# FPGA.net
KiCad netlist of a schematic drawn in Altium Designer
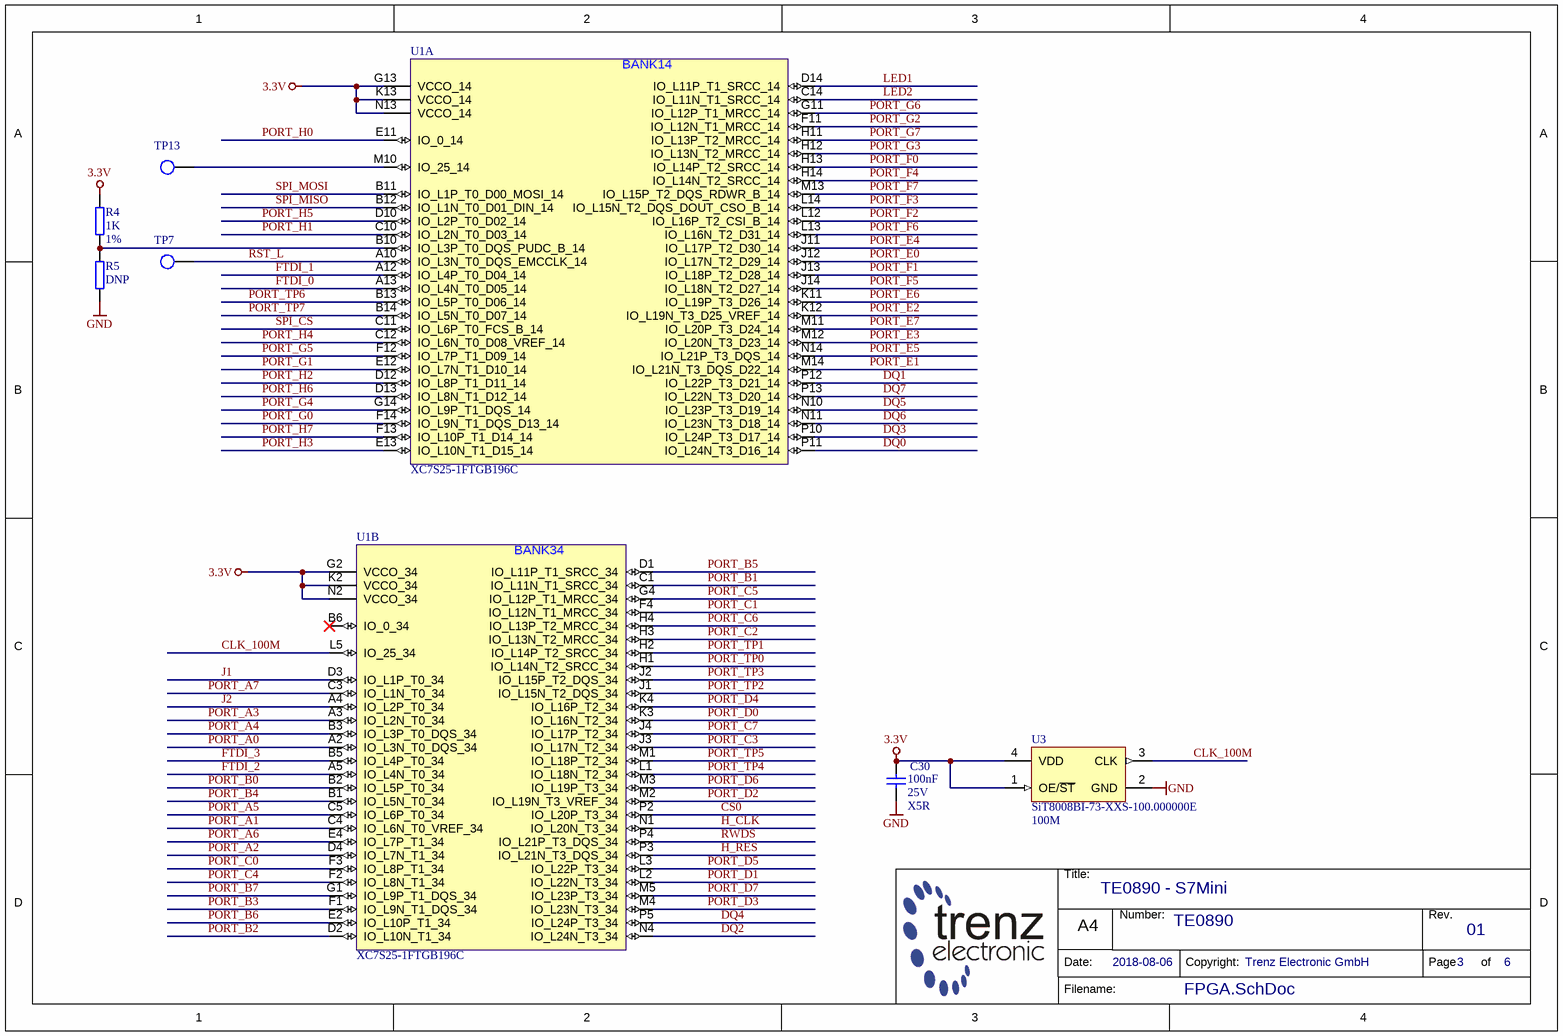
[diagram p0: FPGA.SchDoc]

(export (version "E")
  (design (tool "Eeschema 10.0.6"))
  (components
    (comp (ref "C30")
      (value "100nF")
      (footprint "CAPC1005X55N")
      (description "KON 100nF 25V X5R ±10% SMD BF 1005 (0402)")
      (fields (field (name "VOLTAGE") "25V") (field (name "TECHNOLOGY") "X5R"))
      (libsource (lib "TE") (part "CAP-NP"))
    )
    (comp (ref "R4")
      (value "1K")
      (footprint "RESC1005X40N")
      (description "WID SMD 1K 1% 0,063W  BF 1005 (0402)")
      (fields (field (name "TOLERANCE") "1%"))
      (libsource (lib "TE") (part "RES"))
    )
    (comp (ref "R5")
      (value "DNP")
      (footprint "RESC1005X40N")
      (description "WID SMD BF 1005 (0402) DNP")
      (libsource (lib "TE") (part "RES-NO_BOM"))
    )
    (comp (ref "TP7")
      (value "Testpoint 0.8mm THT")
      (footprint "TP_0.8mm_THT")
      (description "Testpoint 0.8mm TH")
      (libsource (lib "TE") (part "TP_THT"))
    )
    (comp (ref "TP13")
      (value "Testpoint 0.8mm THT")
      (footprint "TP_0.8mm_THT")
      (description "Testpoint 0.8mm TH")
      (libsource (lib "TE") (part "TP_THT"))
    )
    (comp (ref "U1")
      (value "XC7S25-1FTGB196C")
      (footprint "BGA196C100P14X14_1500X1500X155B50N")
      (libsource (lib "TE") (part "XC7S25-1FTGB196"))
    )
    (comp (ref "U3")
      (value "SiT8008BI-73-XXS-100.000000E")
      (footprint "2016")
      (description "SiT8008BI-73-XXS-100.000000E MEMS Oszillator 100MHz")
      (fields (field (name "ALTIUM_VALUE") "100M"))
      (libsource (lib "TE") (part "SiT8103"))
    )
  )
  (nets
    (net (code "1") (name "/CLK_100M") (class "Default")
      (node (ref "U1") (pin "L5") (pinfunction "IO_25_34_L5") (pintype "bidirectional"))
      (node (ref "U3") (pin "3") (pinfunction "CLK_3") (pintype "output"))
    )
    (net (code "2") (name "/CS0") (class "Default")
      (node (ref "U1") (pin "P2") (pinfunction "IO_L20P_T3_34_P2") (pintype "bidirectional"))
    )
    (net (code "3") (name "/DQ0") (class "Default")
      (node (ref "U1") (pin "P11") (pinfunction "IO_L24N_T3_D16_14_P11") (pintype "bidirectional"))
    )
    (net (code "4") (name "/DQ1") (class "Default")
      (node (ref "U1") (pin "P12") (pinfunction "IO_L22P_T3_D21_14_P12") (pintype "bidirectional"))
    )
    (net (code "5") (name "/DQ2") (class "Default")
      (node (ref "U1") (pin "N4") (pinfunction "IO_L24N_T3_34_N4") (pintype "bidirectional"))
    )
    (net (code "6") (name "/DQ3") (class "Default")
      (node (ref "U1") (pin "P10") (pinfunction "IO_L24P_T3_D17_14_P10") (pintype "bidirectional"))
    )
    (net (code "7") (name "/DQ4") (class "Default")
      (node (ref "U1") (pin "P5") (pinfunction "IO_L24P_T3_34_P5") (pintype "bidirectional"))
    )
    (net (code "8") (name "/DQ5") (class "Default")
      (node (ref "U1") (pin "N10") (pinfunction "IO_L23P_T3_D19_14_N10") (pintype "bidirectional"))
    )
    (net (code "9") (name "/DQ6") (class "Default")
      (node (ref "U1") (pin "N11") (pinfunction "IO_L23N_T3_D18_14_N11") (pintype "bidirectional"))
    )
    (net (code "10") (name "/DQ7") (class "Default")
      (node (ref "U1") (pin "P13") (pinfunction "IO_L22N_T3_D20_14_P13") (pintype "bidirectional"))
    )
    (net (code "11") (name "/FTDI_0") (class "Default")
      (node (ref "U1") (pin "A13") (pinfunction "IO_L4N_T0_D05_14_A13") (pintype "bidirectional"))
    )
    (net (code "12") (name "/FTDI_1") (class "Default")
      (node (ref "U1") (pin "A12") (pinfunction "IO_L4P_T0_D04_14_A12") (pintype "bidirectional"))
    )
    (net (code "13") (name "/FTDI_2") (class "Default")
      (node (ref "U1") (pin "A5") (pinfunction "IO_L4N_T0_34_A5") (pintype "bidirectional"))
    )
    (net (code "14") (name "/FTDI_3") (class "Default")
      (node (ref "U1") (pin "B5") (pinfunction "IO_L4P_T0_34_B5") (pintype "bidirectional"))
    )
    (net (code "15") (name "/H_CLK") (class "Default")
      (node (ref "U1") (pin "N1") (pinfunction "IO_L20N_T3_34_N1") (pintype "bidirectional"))
    )
    (net (code "16") (name "/H_RES") (class "Default")
      (node (ref "U1") (pin "P3") (pinfunction "IO_L21N_T3_DQS_34_P3") (pintype "bidirectional"))
    )
    (net (code "17") (name "/J1") (class "Default")
      (node (ref "U1") (pin "D3") (pinfunction "IO_L1P_T0_34_D3") (pintype "bidirectional"))
    )
    (net (code "18") (name "/J2") (class "Default")
      (node (ref "U1") (pin "A4") (pinfunction "IO_L2P_T0_34_A4") (pintype "bidirectional"))
    )
    (net (code "19") (name "/LED1") (class "Default")
      (node (ref "U1") (pin "D14") (pinfunction "IO_L11P_T1_SRCC_14_D14") (pintype "bidirectional"))
    )
    (net (code "20") (name "/LED2") (class "Default")
      (node (ref "U1") (pin "C14") (pinfunction "IO_L11N_T1_SRCC_14_C14") (pintype "bidirectional"))
    )
    (net (code "21") (name "/PORT_A0") (class "Default")
      (node (ref "U1") (pin "A2") (pinfunction "IO_L3N_T0_DQS_34_A2") (pintype "bidirectional"))
    )
    (net (code "22") (name "/PORT_A1") (class "Default")
      (node (ref "U1") (pin "C4") (pinfunction "IO_L6N_T0_VREF_34_C4") (pintype "bidirectional"))
    )
    (net (code "23") (name "/PORT_A2") (class "Default")
      (node (ref "U1") (pin "D4") (pinfunction "IO_L7N_T1_34_D4") (pintype "bidirectional"))
    )
    (net (code "24") (name "/PORT_A3") (class "Default")
      (node (ref "U1") (pin "A3") (pinfunction "IO_L2N_T0_34_A3") (pintype "bidirectional"))
    )
    (net (code "25") (name "/PORT_A4") (class "Default")
      (node (ref "U1") (pin "B3") (pinfunction "IO_L3P_T0_DQS_34_B3") (pintype "bidirectional"))
    )
    (net (code "26") (name "/PORT_A5") (class "Default")
      (node (ref "U1") (pin "C5") (pinfunction "IO_L6P_T0_34_C5") (pintype "bidirectional"))
    )
    (net (code "27") (name "/PORT_A6") (class "Default")
      (node (ref "U1") (pin "E4") (pinfunction "IO_L7P_T1_34_E4") (pintype "bidirectional"))
    )
    (net (code "28") (name "/PORT_A7") (class "Default")
      (node (ref "U1") (pin "C3") (pinfunction "IO_L1N_T0_34_C3") (pintype "bidirectional"))
    )
    (net (code "29") (name "/PORT_B0") (class "Default")
      (node (ref "U1") (pin "B2") (pinfunction "IO_L5P_T0_34_B2") (pintype "bidirectional"))
    )
    (net (code "30") (name "/PORT_B1") (class "Default")
      (node (ref "U1") (pin "C1") (pinfunction "IO_L11N_T1_SRCC_34_C1") (pintype "bidirectional"))
    )
    (net (code "31") (name "/PORT_B2") (class "Default")
      (node (ref "U1") (pin "D2") (pinfunction "IO_L10N_T1_34_D2") (pintype "bidirectional"))
    )
    (net (code "32") (name "/PORT_B3") (class "Default")
      (node (ref "U1") (pin "F1") (pinfunction "IO_L9N_T1_DQS_34_F1") (pintype "bidirectional"))
    )
    (net (code "33") (name "/PORT_B4") (class "Default")
      (node (ref "U1") (pin "B1") (pinfunction "IO_L5N_T0_34_B1") (pintype "bidirectional"))
    )
    (net (code "34") (name "/PORT_B5") (class "Default")
      (node (ref "U1") (pin "D1") (pinfunction "IO_L11P_T1_SRCC_34_D1") (pintype "bidirectional"))
    )
    (net (code "35") (name "/PORT_B6") (class "Default")
      (node (ref "U1") (pin "E2") (pinfunction "IO_L10P_T1_34_E2") (pintype "bidirectional"))
    )
    (net (code "36") (name "/PORT_B7") (class "Default")
      (node (ref "U1") (pin "G1") (pinfunction "IO_L9P_T1_DQS_34_G1") (pintype "bidirectional"))
    )
    (net (code "37") (name "/PORT_C0") (class "Default")
      (node (ref "U1") (pin "F3") (pinfunction "IO_L8P_T1_34_F3") (pintype "bidirectional"))
    )
    (net (code "38") (name "/PORT_C1") (class "Default")
      (node (ref "U1") (pin "F4") (pinfunction "IO_L12N_T1_MRCC_34_F4") (pintype "bidirectional"))
    )
    (net (code "39") (name "/PORT_C2") (class "Default")
      (node (ref "U1") (pin "H3") (pinfunction "IO_L13N_T2_MRCC_34_H3") (pintype "bidirectional"))
    )
    (net (code "40") (name "/PORT_C3") (class "Default")
      (node (ref "U1") (pin "J3") (pinfunction "IO_L17N_T2_34_J3") (pintype "bidirectional"))
    )
    (net (code "41") (name "/PORT_C4") (class "Default")
      (node (ref "U1") (pin "F2") (pinfunction "IO_L8N_T1_34_F2") (pintype "bidirectional"))
    )
    (net (code "42") (name "/PORT_C5") (class "Default")
      (node (ref "U1") (pin "G4") (pinfunction "IO_L12P_T1_MRCC_34_G4") (pintype "bidirectional"))
    )
    (net (code "43") (name "/PORT_C6") (class "Default")
      (node (ref "U1") (pin "H4") (pinfunction "IO_L13P_T2_MRCC_34_H4") (pintype "bidirectional"))
    )
    (net (code "44") (name "/PORT_C7") (class "Default")
      (node (ref "U1") (pin "J4") (pinfunction "IO_L17P_T2_34_J4") (pintype "bidirectional"))
    )
    (net (code "45") (name "/PORT_D0") (class "Default")
      (node (ref "U1") (pin "K3") (pinfunction "IO_L16N_T2_34_K3") (pintype "bidirectional"))
    )
    (net (code "46") (name "/PORT_D1") (class "Default")
      (node (ref "U1") (pin "L2") (pinfunction "IO_L22N_T3_34_L2") (pintype "bidirectional"))
    )
    (net (code "47") (name "/PORT_D2") (class "Default")
      (node (ref "U1") (pin "M2") (pinfunction "IO_L19N_T3_VREF_34_M2") (pintype "bidirectional"))
    )
    (net (code "48") (name "/PORT_D3") (class "Default")
      (node (ref "U1") (pin "M4") (pinfunction "IO_L23N_T3_34_M4") (pintype "bidirectional"))
    )
    (net (code "49") (name "/PORT_D4") (class "Default")
      (node (ref "U1") (pin "K4") (pinfunction "IO_L16P_T2_34_K4") (pintype "bidirectional"))
    )
    (net (code "50") (name "/PORT_D5") (class "Default")
      (node (ref "U1") (pin "L3") (pinfunction "IO_L22P_T3_34_L3") (pintype "bidirectional"))
    )
    (net (code "51") (name "/PORT_D6") (class "Default")
      (node (ref "U1") (pin "M3") (pinfunction "IO_L19P_T3_34_M3") (pintype "bidirectional"))
    )
    (net (code "52") (name "/PORT_D7") (class "Default")
      (node (ref "U1") (pin "M5") (pinfunction "IO_L23P_T3_34_M5") (pintype "bidirectional"))
    )
    (net (code "53") (name "/PORT_E0") (class "Default")
      (node (ref "U1") (pin "J12") (pinfunction "IO_L17N_T2_D29_14_J12") (pintype "bidirectional"))
    )
    (net (code "54") (name "/PORT_E1") (class "Default")
      (node (ref "U1") (pin "M14") (pinfunction "IO_L21N_T3_DQS_D22_14_M14") (pintype "bidirectional"))
    )
    (net (code "55") (name "/PORT_E2") (class "Default")
      (node (ref "U1") (pin "K12") (pinfunction "IO_L19N_T3_D25_VREF_14_K12") (pintype "bidirectional"))
    )
    (net (code "56") (name "/PORT_E3") (class "Default")
      (node (ref "U1") (pin "M12") (pinfunction "IO_L20N_T3_D23_14_M12") (pintype "bidirectional"))
    )
    (net (code "57") (name "/PORT_E4") (class "Default")
      (node (ref "U1") (pin "J11") (pinfunction "IO_L17P_T2_D30_14_J11") (pintype "bidirectional"))
    )
    (net (code "58") (name "/PORT_E5") (class "Default")
      (node (ref "U1") (pin "N14") (pinfunction "IO_L21P_T3_DQS_14_N14") (pintype "bidirectional"))
    )
    (net (code "59") (name "/PORT_E6") (class "Default")
      (node (ref "U1") (pin "K11") (pinfunction "IO_L19P_T3_D26_14_K11") (pintype "bidirectional"))
    )
    (net (code "60") (name "/PORT_E7") (class "Default")
      (node (ref "U1") (pin "M11") (pinfunction "IO_L20P_T3_D24_14_M11") (pintype "bidirectional"))
    )
    (net (code "61") (name "/PORT_F0") (class "Default")
      (node (ref "U1") (pin "H13") (pinfunction "IO_L14P_T2_SRCC_14_H13") (pintype "bidirectional"))
    )
    (net (code "62") (name "/PORT_F1") (class "Default")
      (node (ref "U1") (pin "J13") (pinfunction "IO_L18P_T2_D28_14_J13") (pintype "bidirectional"))
    )
    (net (code "63") (name "/PORT_F2") (class "Default")
      (node (ref "U1") (pin "L12") (pinfunction "IO_L16P_T2_CSI_B_14_L12") (pintype "bidirectional"))
    )
    (net (code "64") (name "/PORT_F3") (class "Default")
      (node (ref "U1") (pin "L14") (pinfunction "IO_L15N_T2_DQS_DOUT_CSO_B_14_L14") (pintype "bidirectional"))
    )
    (net (code "65") (name "/PORT_F4") (class "Default")
      (node (ref "U1") (pin "H14") (pinfunction "IO_L14N_T2_SRCC_14_H14") (pintype "bidirectional"))
    )
    (net (code "66") (name "/PORT_F5") (class "Default")
      (node (ref "U1") (pin "J14") (pinfunction "IO_L18N_T2_D27_14_J14") (pintype "bidirectional"))
    )
    (net (code "67") (name "/PORT_F6") (class "Default")
      (node (ref "U1") (pin "L13") (pinfunction "IO_L16N_T2_D31_14_L13") (pintype "bidirectional"))
    )
    (net (code "68") (name "/PORT_F7") (class "Default")
      (node (ref "U1") (pin "M13") (pinfunction "IO_L15P_T2_DQS_RDWR_B_14_M13") (pintype "bidirectional"))
    )
    (net (code "69") (name "/PORT_G0") (class "Default")
      (node (ref "U1") (pin "F14") (pinfunction "IO_L9N_T1_DQS_D13_14_F14") (pintype "bidirectional"))
    )
    (net (code "70") (name "/PORT_G1") (class "Default")
      (node (ref "U1") (pin "E12") (pinfunction "IO_L7N_T1_D10_14_E12") (pintype "bidirectional"))
    )
    (net (code "71") (name "/PORT_G2") (class "Default")
      (node (ref "U1") (pin "F11") (pinfunction "IO_L12N_T1_MRCC_14_F11") (pintype "bidirectional"))
    )
    (net (code "72") (name "/PORT_G3") (class "Default")
      (node (ref "U1") (pin "H12") (pinfunction "IO_L13N_T2_MRCC_14_H12") (pintype "bidirectional"))
    )
    (net (code "73") (name "/PORT_G4") (class "Default")
      (node (ref "U1") (pin "G14") (pinfunction "IO_L9P_T1_DQS_14_G14") (pintype "bidirectional"))
    )
    (net (code "74") (name "/PORT_G5") (class "Default")
      (node (ref "U1") (pin "F12") (pinfunction "IO_L7P_T1_D09_14_F12") (pintype "bidirectional"))
    )
    (net (code "75") (name "/PORT_G6") (class "Default")
      (node (ref "U1") (pin "G11") (pinfunction "IO_L12P_T1_MRCC_14_G11") (pintype "bidirectional"))
    )
    (net (code "76") (name "/PORT_G7") (class "Default")
      (node (ref "U1") (pin "H11") (pinfunction "IO_L13P_T2_MRCC_14_H11") (pintype "bidirectional"))
    )
    (net (code "77") (name "/PORT_H0") (class "Default")
      (node (ref "U1") (pin "E11") (pinfunction "IO_0_14_E11") (pintype "bidirectional"))
    )
    (net (code "78") (name "/PORT_H1") (class "Default")
      (node (ref "U1") (pin "C10") (pinfunction "IO_L2N_T0_D03_14_C10") (pintype "bidirectional"))
    )
    (net (code "79") (name "/PORT_H2") (class "Default")
      (node (ref "U1") (pin "D12") (pinfunction "IO_L8P_T1_D11_14_D12") (pintype "bidirectional"))
    )
    (net (code "80") (name "/PORT_H3") (class "Default")
      (node (ref "U1") (pin "E13") (pinfunction "IO_L10N_T1_D15_14_E13") (pintype "bidirectional"))
    )
    (net (code "81") (name "/PORT_H4") (class "Default")
      (node (ref "U1") (pin "C12") (pinfunction "IO_L6N_T0_D08_VREF_14_C12") (pintype "bidirectional"))
    )
    (net (code "82") (name "/PORT_H5") (class "Default")
      (node (ref "U1") (pin "D10") (pinfunction "IO_L2P_T0_D02_14_D10") (pintype "bidirectional"))
    )
    (net (code "83") (name "/PORT_H6") (class "Default")
      (node (ref "U1") (pin "D13") (pinfunction "IO_L8N_T1_D12_14_D13") (pintype "bidirectional"))
    )
    (net (code "84") (name "/PORT_H7") (class "Default")
      (node (ref "U1") (pin "F13") (pinfunction "IO_L10P_T1_D14_14_F13") (pintype "bidirectional"))
    )
    (net (code "85") (name "/PORT_TP0") (class "Default")
      (node (ref "U1") (pin "H1") (pinfunction "IO_L14N_T2_SRCC_34_H1") (pintype "bidirectional"))
    )
    (net (code "86") (name "/PORT_TP1") (class "Default")
      (node (ref "U1") (pin "H2") (pinfunction "IO_L14P_T2_SRCC_34_H2") (pintype "bidirectional"))
    )
    (net (code "87") (name "/PORT_TP2") (class "Default")
      (node (ref "U1") (pin "J1") (pinfunction "IO_L15N_T2_DQS_34_J1") (pintype "bidirectional"))
    )
    (net (code "88") (name "/PORT_TP3") (class "Default")
      (node (ref "U1") (pin "J2") (pinfunction "IO_L15P_T2_DQS_34_J2") (pintype "bidirectional"))
    )
    (net (code "89") (name "/PORT_TP4") (class "Default")
      (node (ref "U1") (pin "L1") (pinfunction "IO_L18N_T2_34_L1") (pintype "bidirectional"))
    )
    (net (code "90") (name "/PORT_TP5") (class "Default")
      (node (ref "U1") (pin "M1") (pinfunction "IO_L18P_T2_34_M1") (pintype "bidirectional"))
    )
    (net (code "91") (name "/PORT_TP6") (class "Default")
      (node (ref "U1") (pin "B13") (pinfunction "IO_L5P_T0_D06_14_B13") (pintype "bidirectional"))
    )
    (net (code "92") (name "/PORT_TP7") (class "Default")
      (node (ref "U1") (pin "B14") (pinfunction "IO_L5N_T0_D07_14_B14") (pintype "bidirectional"))
    )
    (net (code "93") (name "/RST_L") (class "Default")
      (node (ref "TP7") (pin "1") (pintype "passive"))
      (node (ref "U1") (pin "A10") (pinfunction "IO_L3N_T0_DQS_EMCCLK_14_A10") (pintype "bidirectional"))
    )
    (net (code "94") (name "/RWDS") (class "Default")
      (node (ref "U1") (pin "P4") (pinfunction "IO_L21P_T3_DQS_34_P4") (pintype "bidirectional"))
    )
    (net (code "95") (name "/SPI_CS") (class "Default")
      (node (ref "U1") (pin "C11") (pinfunction "IO_L6P_T0_FCS_B_14_C11") (pintype "bidirectional"))
    )
    (net (code "96") (name "/SPI_MISO") (class "Default")
      (node (ref "U1") (pin "B12") (pinfunction "IO_L1N_T0_D01_DIN_14_B12") (pintype "bidirectional"))
    )
    (net (code "97") (name "/SPI_MOSI") (class "Default")
      (node (ref "U1") (pin "B11") (pinfunction "IO_L1P_T0_D00_MOSI_14_B11") (pintype "bidirectional"))
    )
    (net (code "98") (name "3.3V") (class "Default")
      (node (ref "C30") (pin "1") (pinfunction "1_1") (pintype "passive"))
      (node (ref "R4") (pin "1") (pinfunction "1_1") (pintype "passive"))
      (node (ref "U1") (pin "G13") (pinfunction "VCCO_14_G13") (pintype "power_in"))
      (node (ref "U1") (pin "G2") (pinfunction "VCCO_34_G2") (pintype "power_in"))
      (node (ref "U1") (pin "K13") (pinfunction "VCCO_14_K13") (pintype "power_in"))
      (node (ref "U1") (pin "K2") (pinfunction "VCCO_34_K2") (pintype "power_in"))
      (node (ref "U1") (pin "N13") (pinfunction "VCCO_14_N13") (pintype "power_in"))
      (node (ref "U1") (pin "N2") (pinfunction "VCCO_34_N2") (pintype "power_in"))
      (node (ref "U3") (pin "1") (pinfunction "OE/~{ST}_1") (pintype "input"))
      (node (ref "U3") (pin "4") (pinfunction "VDD_4") (pintype "power_in"))
    )
    (net (code "99") (name "GND") (class "Default")
      (node (ref "C30") (pin "2") (pinfunction "2_2") (pintype "passive"))
      (node (ref "R5") (pin "2") (pinfunction "2_2") (pintype "passive"))
      (node (ref "U3") (pin "2") (pinfunction "GND_2") (pintype "power_in"))
    )
    (net (code "100") (name "Net-(U1A-IO_25_14)") (class "Default")
      (node (ref "TP13") (pin "1") (pintype "passive"))
      (node (ref "U1") (pin "M10") (pinfunction "IO_25_14_M10") (pintype "bidirectional"))
    )
    (net (code "101") (name "Net-(U1A-IO_L3P_T0_DQS_PUDC_B_14)") (class "Default")
      (node (ref "R4") (pin "2") (pinfunction "2_2") (pintype "passive"))
      (node (ref "R5") (pin "1") (pinfunction "1_1") (pintype "passive"))
      (node (ref "U1") (pin "B10") (pinfunction "IO_L3P_T0_DQS_PUDC_B_14_B10") (pintype "bidirectional"))
    )
    (net (code "102") (name "unconnected-(U1B-IO_0_34-PadB6)") (class "Default")
      (node (ref "U1") (pin "B6") (pinfunction "IO_0_34_B6") (pintype "bidirectional+no_connect"))
    )
  )
)
